# Sheet1.net
KiCad netlist of a schematic drawn in Altium Designer
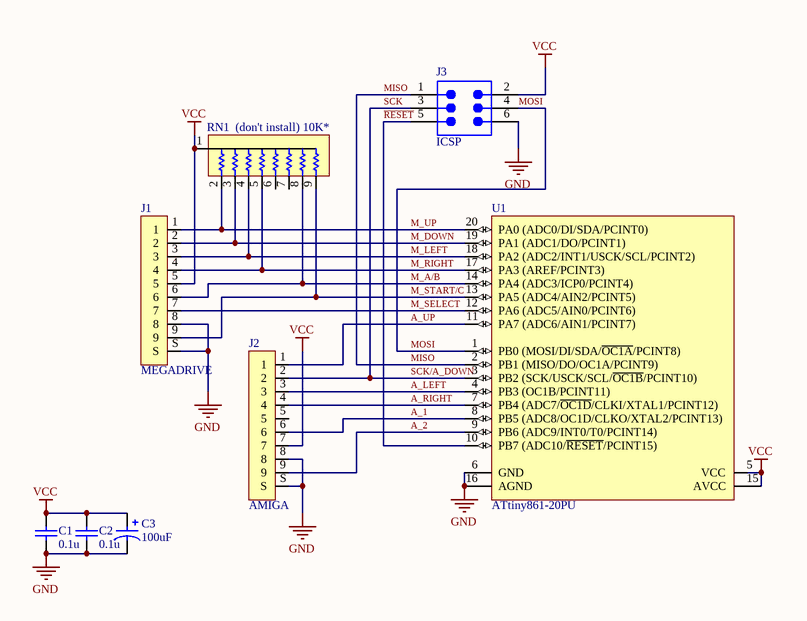
[diagram p0: Sheet1.SchDoc]

(export (version "E")
  (design (tool "Eeschema 10.0.6"))
  (components
    (comp (ref "C1")
      (value "0.1u")
      (footprint "PCB-gb6o2snpw67z713rrl5r-1")
      (description "Generic Ceramic capacitor")
      (libsource (lib "CommunityVault") (part "CMP-mck1uwszlh1jwp1a4juu-2"))
    )
    (comp (ref "C2")
      (value "0.1u")
      (footprint "PCB-gb6o2snpw67z713rrl5r-1")
      (description "Generic Ceramic capacitor")
      (libsource (lib "CommunityVault") (part "CMP-mck1uwszlh1jwp1a4juu-2"))
    )
    (comp (ref "C3")
      (value "100uF")
      (footprint "PCB-zkzjfh55ek2i5yq9ppya-1")
      (description "Electrolytic capacitor, 2.5mm lead spacing")
      (libsource (lib "FavoritesLibrary") (part "SYM-2ourdj6tgxzh24x23r42-1"))
    )
    (comp (ref "J1")
      (value "MEGADRIVE")
      (footprint "PCB-narckcn0kuokny0s6axh-1")
      (description "D-Sub 9 Male Right angle")
      (libsource (lib "CommunityVault") (part "SYM-zxqw2vts6hu4resmcbpc-1"))
    )
    (comp (ref "J2")
      (value "AMIGA")
      (footprint "PCB-x3gdmgk5yw5hhg2skuh0-1")
      (description "D-Sub 9 Female - Right angle")
      (libsource (lib "FavoritesLibrary") (part "SYM-et3ztss3jq69ayfxonkj-1"))
    )
    (comp (ref "J3")
      (value "ICSP")
      (footprint "2X03")
      (fields (field (name "MANUFACTURER PART NUMBER") "826656-3"))
      (libsource (lib "CommunityVault") (part "Header_3x2"))
    )
    (comp (ref "RN1")
      (value "10K*")
      (footprint "PCB-tw4qvmihfhj6qswmfh4l-1")
      (description "8 resistor (9 pin) bussed resistor network")
      (libsource (lib "CommunityVault") (part "CMP-ho91cd316paqm6me0i9o-1"))
    )
    (comp (ref "U1")
      (value "ATtiny861-20PU")
      (footprint "20P3")
      (libsource (lib "FavoritesLibrary") (part "MC-8B-ATT261A-IL20"))
    )
  )
  (nets
    (net (code "1") (name "/A_1") (class "Default")
      (node (ref "J2") (pin "6") (pinfunction "6_6") (pintype "passive"))
      (node (ref "U1") (pin "8") (pinfunction "PB5_(ADC8/OC1D/CLKO/XTAL2/PCINT13)_8") (pintype "bidirectional"))
    )
    (net (code "2") (name "/A_2") (class "Default")
      (node (ref "J2") (pin "9") (pinfunction "9_9") (pintype "passive"))
      (node (ref "U1") (pin "9") (pinfunction "PB6_(ADC9/INT0/T0/PCINT14)_9") (pintype "bidirectional"))
    )
    (net (code "3") (name "/A_LEFT") (class "Default")
      (node (ref "J2") (pin "3") (pinfunction "3_3") (pintype "passive"))
      (node (ref "U1") (pin "4") (pinfunction "PB3_(OC1B/PCINT11)_4") (pintype "bidirectional"))
    )
    (net (code "4") (name "/A_RIGHT") (class "Default")
      (node (ref "J2") (pin "4") (pinfunction "4_4") (pintype "passive"))
      (node (ref "U1") (pin "7") (pinfunction "PB4_(ADC7/~{OC1D}/CLKI/XTAL1/PCINT12)_7") (pintype "bidirectional"))
    )
    (net (code "5") (name "/A_UP") (class "Default")
      (node (ref "J2") (pin "1") (pinfunction "1_1") (pintype "passive"))
      (node (ref "U1") (pin "11") (pinfunction "PA7_(ADC6/AIN1/PCINT7)_11") (pintype "bidirectional"))
    )
    (net (code "6") (name "/MISO") (class "Default")
      (node (ref "J3") (pin "1") (pinfunction "1_1") (pintype "passive"))
      (node (ref "U1") (pin "2") (pinfunction "PB1_(MISO/DO/OC1A/PCINT9)_2") (pintype "bidirectional"))
    )
    (net (code "7") (name "/MOSI") (class "Default")
      (node (ref "J3") (pin "4") (pinfunction "4_4") (pintype "passive"))
      (node (ref "U1") (pin "1") (pinfunction "PB0_(MOSI/DI/SDA/~{OC1A}/PCINT8)_1") (pintype "bidirectional"))
    )
    (net (code "8") (name "/M_A{slash}B") (class "Default")
      (node (ref "J1") (pin "6") (pinfunction "6_6") (pintype "passive"))
      (node (ref "RN1") (pin "8") (pinfunction "8_8") (pintype "passive"))
      (node (ref "U1") (pin "14") (pinfunction "PA4_(ADC3/ICP0/PCINT4)_14") (pintype "bidirectional"))
    )
    (net (code "9") (name "/M_DOWN") (class "Default")
      (node (ref "J1") (pin "2") (pinfunction "2_2") (pintype "passive"))
      (node (ref "RN1") (pin "3") (pinfunction "3_3") (pintype "passive"))
      (node (ref "U1") (pin "19") (pinfunction "PA1_(ADC1/DO/PCINT1)_19") (pintype "bidirectional"))
    )
    (net (code "10") (name "/M_LEFT") (class "Default")
      (node (ref "J1") (pin "3") (pinfunction "3_3") (pintype "passive"))
      (node (ref "RN1") (pin "4") (pinfunction "4_4") (pintype "passive"))
      (node (ref "U1") (pin "18") (pinfunction "PA2_(ADC2/INT1/USCK/SCL/PCINT2)_18") (pintype "bidirectional"))
    )
    (net (code "11") (name "/M_RIGHT") (class "Default")
      (node (ref "J1") (pin "4") (pinfunction "4_4") (pintype "passive"))
      (node (ref "RN1") (pin "5") (pinfunction "5_5") (pintype "passive"))
      (node (ref "U1") (pin "17") (pinfunction "PA3_(AREF/PCINT3)_17") (pintype "bidirectional"))
    )
    (net (code "12") (name "/M_SELECT") (class "Default")
      (node (ref "J1") (pin "7") (pinfunction "7_7") (pintype "passive"))
      (node (ref "U1") (pin "12") (pinfunction "PA6_(ADC5/AIN0/PCINT6)_12") (pintype "bidirectional"))
    )
    (net (code "13") (name "/M_START{slash}C") (class "Default")
      (node (ref "J1") (pin "9") (pinfunction "9_9") (pintype "passive"))
      (node (ref "RN1") (pin "9") (pinfunction "9_9") (pintype "passive"))
      (node (ref "U1") (pin "13") (pinfunction "PA5_(ADC4/AIN2/PCINT5)_13") (pintype "bidirectional"))
    )
    (net (code "14") (name "/M_UP") (class "Default")
      (node (ref "J1") (pin "1") (pinfunction "1_1") (pintype "passive"))
      (node (ref "RN1") (pin "2") (pinfunction "2_2") (pintype "passive"))
      (node (ref "U1") (pin "20") (pinfunction "PA0_(ADC0/DI/SDA/PCINT0)_20") (pintype "bidirectional"))
    )
    (net (code "15") (name "/SCK") (class "Default")
      (node (ref "J2") (pin "2") (pinfunction "2_2") (pintype "passive"))
      (node (ref "J3") (pin "3") (pinfunction "3_3") (pintype "passive"))
      (node (ref "U1") (pin "3") (pinfunction "PB2_(SCK/USCK/SCL/~{OC1B}/PCINT10)_3") (pintype "bidirectional"))
    )
    (net (code "16") (name "/~{RESET}") (class "Default")
      (node (ref "J3") (pin "5") (pinfunction "5_5") (pintype "passive"))
      (node (ref "U1") (pin "10") (pinfunction "PB7_(ADC10/~{RESET}/PCINT15)_10") (pintype "bidirectional"))
    )
    (net (code "17") (name "GND") (class "Default")
      (node (ref "C1") (pin "1") (pinfunction "1_1") (pintype "passive"))
      (node (ref "C2") (pin "1") (pinfunction "1_1") (pintype "passive"))
      (node (ref "C3") (pin "2") (pinfunction "2_2") (pintype "passive"))
      (node (ref "J1") (pin "8") (pinfunction "8_8") (pintype "passive"))
      (node (ref "J1") (pin "S") (pinfunction "S_S") (pintype "passive"))
      (node (ref "J2") (pin "8") (pinfunction "8_8") (pintype "passive"))
      (node (ref "J2") (pin "S") (pinfunction "S_S") (pintype "passive"))
      (node (ref "J3") (pin "6") (pinfunction "6_6") (pintype "passive"))
      (node (ref "U1") (pin "16") (pinfunction "AGND_16") (pintype "power_in"))
      (node (ref "U1") (pin "6") (pinfunction "GND_6") (pintype "power_in"))
    )
    (net (code "18") (name "VCC") (class "Default")
      (node (ref "C1") (pin "2") (pinfunction "2_2") (pintype "passive"))
      (node (ref "C2") (pin "2") (pinfunction "2_2") (pintype "passive"))
      (node (ref "C3") (pin "1") (pinfunction "1_1") (pintype "passive"))
      (node (ref "J1") (pin "5") (pinfunction "5_5") (pintype "passive"))
      (node (ref "J2") (pin "7") (pinfunction "7_7") (pintype "passive"))
      (node (ref "J3") (pin "2") (pinfunction "2_2") (pintype "passive"))
      (node (ref "RN1") (pin "1") (pinfunction "1_1") (pintype "passive"))
      (node (ref "U1") (pin "15") (pinfunction "AVCC_15") (pintype "power_in"))
      (node (ref "U1") (pin "5") (pinfunction "VCC_5") (pintype "power_in"))
    )
    (net (code "19") (name "unconnected-(J2-Pad5)") (class "Default")
      (node (ref "J2") (pin "5") (pinfunction "5_5") (pintype "passive"))
    )
    (net (code "20") (name "unconnected-(RN1-Pad6)") (class "Default")
      (node (ref "RN1") (pin "6") (pinfunction "6_6") (pintype "passive"))
    )
    (net (code "21") (name "unconnected-(RN1-Pad7)") (class "Default")
      (node (ref "RN1") (pin "7") (pinfunction "7_7") (pintype "passive"))
    )
  )
)
